# DP_UART.net
KiCad netlist of a schematic drawn in Altium Designer
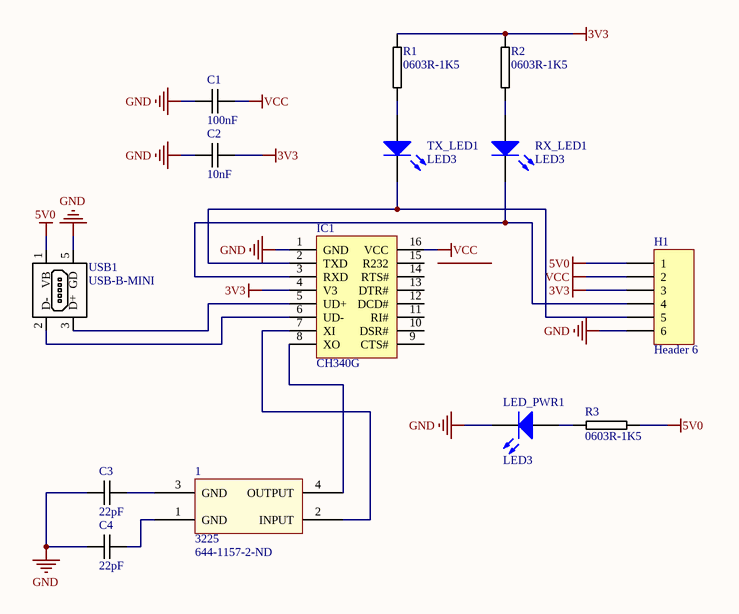
[diagram p0: DP_UART.SchDoc]

(export (version "E")
  (design (tool "Eeschema 10.0.6"))
  (components
    (comp (ref "1")
      (value "3225")
      (footprint "XTAL 3225")
      (fields (field (name "SUPPLIER PART NUMBER 1") "644-1157-2-ND"))
      (libsource (lib "RVA_Reference_Crystal Oscillator_SMD") (part "3225 Quartz"))
    )
    (comp (ref "C1")
      (value "100nF")
      (footprint "0603C-GENERIC")
      (description "CAPACITOR 0603 CERAMIC")
      (fields
        (field (name "MANUFACTURER PART NUMBER") "C1608X7R1E104K")
        (field (name "MANUFACTURER") "TDK Corporation")
      )
      (libsource (lib "RVA_Passives_Capacitors_0603") (part "Passives_Capacitors_0603_100NF-25V-X7R-TDK"))
    )
    (comp (ref "C2")
      (value "10nF")
      (footprint "0603C-GENERIC")
      (description "CAPACITOR 0603 CERAMIC")
      (fields
        (field (name "MANUFACTURER PART NUMBER") "GRM188R71H103KA01D")
        (field (name "MANUFACTURER") "Murata Electronics North America")
      )
      (libsource (lib "RVA_Passives_Capacitors_0603") (part "Passives_Capacitors_0603_10NF-50V-X7R-MUR"))
    )
    (comp (ref "C3")
      (value "22pF")
      (footprint "0603C-GENERIC")
      (description "CAPACITOR 0603 CERAMIC")
      (fields (field (name "TOLERANCE") "±5%") (field (name "MANUFACTURER PART NUMBER") "ECJ-1VC1H220J"))
      (libsource (lib "RVA_Passives_Capacitors_0603") (part "Passives_Capacitors_0603_22PF-50V-C0G-PAN"))
    )
    (comp (ref "C4")
      (value "22pF")
      (footprint "0603C-GENERIC")
      (description "CAPACITOR 0603 CERAMIC")
      (fields (field (name "TOLERANCE") "±5%") (field (name "MANUFACTURER PART NUMBER") "ECJ-1VC1H220J"))
      (libsource (lib "RVA_Passives_Capacitors_0603") (part "Passives_Capacitors_0603_22PF-50V-C0G-PAN"))
    )
    (comp (ref "H1")
      (value "Header 6")
      (footprint "HDR1X6")
      (description "Header, 6-Pin")
      (fields (field (name "PUBLISHER") "Altium Limited"))
      (libsource (lib "Miscellaneous Connectors") (part "Header 6"))
    )
    (comp (ref "IC1") (value "CH340G") (footprint "SO16") (libsource (lib "CH340") (part "CH340G")))
    (comp (ref "LED_PWR1")
      (value "LED3")
      (footprint "3.5X2.8X1.9")
      (description "Typical BLUE SiC LED")
      (fields (field (name "PUBLISHER") "Altium Limited"))
      (libsource (lib "Miscellaneous Devices") (part "LED3"))
    )
    (comp (ref "R1")
      (value "0603R-1K5")
      (footprint "0603R-1k5")
      (description "GENERIC RESISTOR 0603")
      (fields (field (name "MANUFACTURER PART NUMBER") "RMCF 1/16 15K 1% R") (field (name "TOLERANCE") "±1%"))
      (libsource (lib "RVA_Passives_Resistors_0603") (part "0603R-1K5"))
    )
    (comp (ref "R2")
      (value "0603R-1K5")
      (footprint "0603R-1k5")
      (description "GENERIC RESISTOR 0603")
      (fields (field (name "MANUFACTURER PART NUMBER") "RMCF 1/16 15K 1% R") (field (name "TOLERANCE") "±1%"))
      (libsource (lib "RVA_Passives_Resistors_0603") (part "0603R-1K5"))
    )
    (comp (ref "R3")
      (value "0603R-1K5")
      (footprint "0603R-1k5")
      (description "GENERIC RESISTOR 0603")
      (fields (field (name "MANUFACTURER PART NUMBER") "RMCF 1/16 15K 1% R") (field (name "TOLERANCE") "±1%"))
      (libsource (lib "RVA_Passives_Resistors_0603") (part "0603R-1K5"))
    )
    (comp (ref "RX_LED1")
      (value "LED3")
      (footprint "3.5X2.8X1.9")
      (description "Typical BLUE SiC LED")
      (fields (field (name "PUBLISHER") "Altium Limited"))
      (libsource (lib "Miscellaneous Devices") (part "LED3"))
    )
    (comp (ref "TX_LED1")
      (value "LED3")
      (footprint "3.5X2.8X1.9")
      (description "Typical BLUE SiC LED")
      (fields (field (name "PUBLISHER") "Altium Limited"))
      (libsource (lib "Miscellaneous Devices") (part "LED3"))
    )
    (comp (ref "USB1")
      (value "USB-B-MINI")
      (footprint "USB-MINI-B")
      (description "MINI USB B DEVICE CONNECTOR")
      (libsource (lib "RVA_Connector_USB_THT") (part "Connector_USB_THT_USB-B-MINI"))
    )
  )
  (nets
    (net (code "1") (name "3V3") (class "Default")
      (node (ref "C2") (pin "2") (pintype "passive"))
      (node (ref "H1") (pin "3") (pinfunction "3_3") (pintype "passive"))
      (node (ref "IC1") (pin "4") (pinfunction "V3_4") (pintype "passive"))
      (node (ref "R1") (pin "1") (pintype "passive"))
      (node (ref "R2") (pin "1") (pintype "passive"))
    )
    (net (code "2") (name "5V0") (class "Default")
      (node (ref "H1") (pin "1") (pinfunction "1_1") (pintype "passive"))
      (node (ref "R3") (pin "1") (pintype "passive"))
      (node (ref "USB1") (pin "1") (pinfunction "VB_1") (pintype "passive"))
    )
    (net (code "3") (name "GND") (class "Default")
      (node (ref "C1") (pin "1") (pintype "passive"))
      (node (ref "C2") (pin "1") (pintype "passive"))
      (node (ref "C3") (pin "1") (pintype "passive"))
      (node (ref "C4") (pin "1") (pintype "passive"))
      (node (ref "H1") (pin "6") (pinfunction "6_6") (pintype "passive"))
      (node (ref "IC1") (pin "1") (pinfunction "GND_1") (pintype "passive"))
      (node (ref "LED_PWR1") (pin "2") (pinfunction "K_2") (pintype "passive"))
      (node (ref "USB1") (pin "5") (pinfunction "GD_5") (pintype "passive"))
    )
    (net (code "4") (name "Net-(1-GND-Pad1)") (class "Default")
      (node (ref "1") (pin "1") (pinfunction "GND_1") (pintype "passive"))
      (node (ref "C4") (pin "2") (pintype "passive"))
    )
    (net (code "5") (name "Net-(1-GND-Pad3)") (class "Default")
      (node (ref "1") (pin "3") (pinfunction "GND_3") (pintype "passive"))
      (node (ref "C3") (pin "2") (pintype "passive"))
    )
    (net (code "6") (name "Net-(1-INPUT)") (class "Default")
      (node (ref "1") (pin "2") (pinfunction "INPUT_2") (pintype "passive"))
      (node (ref "IC1") (pin "7") (pinfunction "XI_7") (pintype "passive"))
    )
    (net (code "7") (name "Net-(1-OUTPUT)") (class "Default")
      (node (ref "1") (pin "4") (pinfunction "OUTPUT_4") (pintype "passive"))
      (node (ref "IC1") (pin "8") (pinfunction "XO_8") (pintype "passive"))
    )
    (net (code "8") (name "Net-(IC1-RXD)") (class "Default")
      (node (ref "H1") (pin "4") (pinfunction "4_4") (pintype "passive"))
      (node (ref "IC1") (pin "3") (pinfunction "RXD_3") (pintype "passive"))
      (node (ref "RX_LED1") (pin "2") (pinfunction "K_2") (pintype "passive"))
    )
    (net (code "9") (name "Net-(IC1-TXD)") (class "Default")
      (node (ref "H1") (pin "5") (pinfunction "5_5") (pintype "passive"))
      (node (ref "IC1") (pin "2") (pinfunction "TXD_2") (pintype "passive"))
      (node (ref "TX_LED1") (pin "2") (pinfunction "K_2") (pintype "passive"))
    )
    (net (code "10") (name "Net-(IC1-UD+)") (class "Default")
      (node (ref "IC1") (pin "5") (pinfunction "UD+_5") (pintype "passive"))
      (node (ref "USB1") (pin "3") (pinfunction "D+_3") (pintype "passive"))
    )
    (net (code "11") (name "Net-(IC1-UD-)") (class "Default")
      (node (ref "IC1") (pin "6") (pinfunction "UD-_6") (pintype "passive"))
      (node (ref "USB1") (pin "2") (pinfunction "D-_2") (pintype "passive"))
    )
    (net (code "12") (name "Net-(LED_PWR1-A)") (class "Default")
      (node (ref "LED_PWR1") (pin "1") (pinfunction "A_1") (pintype "passive"))
      (node (ref "R3") (pin "2") (pintype "passive"))
    )
    (net (code "13") (name "Net-(RX_LED1-A)") (class "Default")
      (node (ref "R2") (pin "2") (pintype "passive"))
      (node (ref "RX_LED1") (pin "1") (pinfunction "A_1") (pintype "passive"))
    )
    (net (code "14") (name "Net-(TX_LED1-A)") (class "Default")
      (node (ref "R1") (pin "2") (pintype "passive"))
      (node (ref "TX_LED1") (pin "1") (pinfunction "A_1") (pintype "passive"))
    )
    (net (code "15") (name "VCC") (class "Default")
      (node (ref "C1") (pin "2") (pintype "passive"))
      (node (ref "H1") (pin "2") (pinfunction "2_2") (pintype "passive"))
      (node (ref "IC1") (pin "16") (pinfunction "VCC_16") (pintype "passive"))
    )
    (net (code "16") (name "unconnected-(IC1-CTS#-Pad9)") (class "Default")
      (node (ref "IC1") (pin "9") (pinfunction "CTS#_9") (pintype "passive"))
    )
    (net (code "17") (name "unconnected-(IC1-DCD#-Pad12)") (class "Default")
      (node (ref "IC1") (pin "12") (pinfunction "DCD#_12") (pintype "passive"))
    )
    (net (code "18") (name "unconnected-(IC1-DSR#-Pad10)") (class "Default")
      (node (ref "IC1") (pin "10") (pinfunction "DSR#_10") (pintype "passive"))
    )
    (net (code "19") (name "unconnected-(IC1-DTR#-Pad13)") (class "Default")
      (node (ref "IC1") (pin "13") (pinfunction "DTR#_13") (pintype "passive"))
    )
    (net (code "20") (name "unconnected-(IC1-R232-Pad15)") (class "Default")
      (node (ref "IC1") (pin "15") (pinfunction "R232_15") (pintype "passive"))
    )
    (net (code "21") (name "unconnected-(IC1-RI#-Pad11)") (class "Default")
      (node (ref "IC1") (pin "11") (pinfunction "RI#_11") (pintype "passive"))
    )
    (net (code "22") (name "unconnected-(IC1-RTS#-Pad14)") (class "Default")
      (node (ref "IC1") (pin "14") (pinfunction "RTS#_14") (pintype "passive"))
    )
  )
)
